# PSU_VCC3V3_Buck.net
KiCad netlist of a schematic drawn in Altium Designer
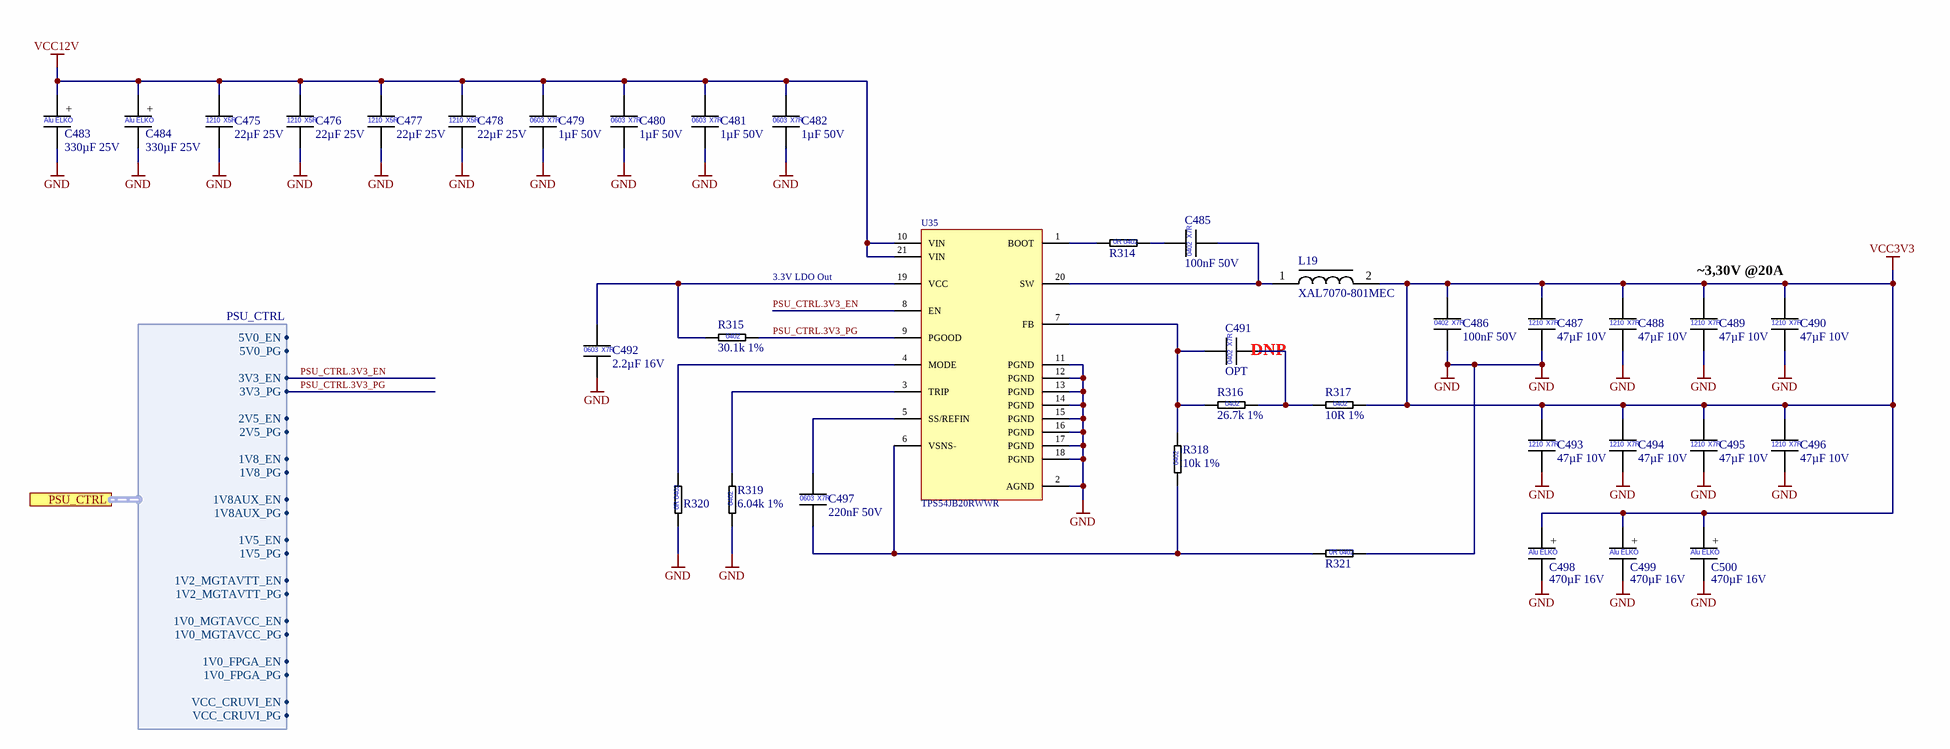
[diagram p0: PSU_VCC3V3_Buck.SchDoc]

(export (version "E")
  (design (tool "Eeschema 10.0.6"))
  (components
    (comp (ref "C475")
      (value "22µF 25V")
      (footprint "Cap:CAP_1210")
      (description "Multilayer Ceramic Capacitors MLCC - SMD/SMT 1210 25VDC")
      (libsource (lib "Cap") (part "CAP_1210_22µF_25V"))
    )
    (comp (ref "C476")
      (value "22µF 25V")
      (footprint "Cap:CAP_1210")
      (description "Multilayer Ceramic Capacitors MLCC - SMD/SMT 1210 25VDC")
      (libsource (lib "Cap") (part "CAP_1210_22µF_25V"))
    )
    (comp (ref "C477")
      (value "22µF 25V")
      (footprint "Cap:CAP_1210")
      (description "Multilayer Ceramic Capacitors MLCC - SMD/SMT 1210 25VDC")
      (libsource (lib "Cap") (part "CAP_1210_22µF_25V"))
    )
    (comp (ref "C478")
      (value "22µF 25V")
      (footprint "Cap:CAP_1210")
      (description "Multilayer Ceramic Capacitors MLCC - SMD/SMT 1210 25VDC")
      (libsource (lib "Cap") (part "CAP_1210_22µF_25V"))
    )
    (comp (ref "C479")
      (value "1µF 50V")
      (footprint "CAP_0603")
      (description "Multilayer Ceramic Capacitors MLCC - SMD/SMT 50V 1uF X7R 0603 10%")
      (libsource (lib "Cap") (part "CAP_0603_1µF_50V_X7R_10%"))
    )
    (comp (ref "C480")
      (value "1µF 50V")
      (footprint "CAP_0603")
      (description "Multilayer Ceramic Capacitors MLCC - SMD/SMT 50V 1uF X7R 0603 10%")
      (libsource (lib "Cap") (part "CAP_0603_1µF_50V_X7R_10%"))
    )
    (comp (ref "C481")
      (value "1µF 50V")
      (footprint "CAP_0603")
      (description "Multilayer Ceramic Capacitors MLCC - SMD/SMT 50V 1uF X7R 0603 10%")
      (libsource (lib "Cap") (part "CAP_0603_1µF_50V_X7R_10%"))
    )
    (comp (ref "C482")
      (value "1µF 50V")
      (footprint "CAP_0603")
      (description "Multilayer Ceramic Capacitors MLCC - SMD/SMT 50V 1uF X7R 0603 10%")
      (libsource (lib "Cap") (part "CAP_0603_1µF_50V_X7R_10%"))
    )
    (comp (ref "C483")
      (value "330µF 25V")
      (footprint "Cap:WCAP-PTG5_D10H12.5")
      (description "Organische Polymer-Aluminiumkondensatoren 330uF 25 Volts 20% AEC-Q200")
      (libsource (lib "Cap") (part "CAP_D10L12.5_330µF_25V"))
    )
    (comp (ref "C484")
      (value "330µF 25V")
      (footprint "Cap:WCAP-PTG5_D10H12.5")
      (description "Organische Polymer-Aluminiumkondensatoren 330uF 25 Volts 20% AEC-Q200")
      (libsource (lib "Cap") (part "CAP_D10L12.5_330µF_25V"))
    )
    (comp (ref "C485")
      (value "100nF 50V")
      (footprint "Cap:CAP_0402")
      (description "Multilayer Ceramic Capacitors MLCC - SMD/SMT 0402 50VDC")
      (libsource (lib "") (part "CAP_0402_100nF_50V_1"))
    )
    (comp (ref "C486")
      (value "100nF 50V")
      (footprint "Cap:CAP_0402")
      (description "Multilayer Ceramic Capacitors MLCC - SMD/SMT 0402 50VDC")
      (libsource (lib "Cap") (part "CAP_0402_100nF_50V"))
    )
    (comp (ref "C487")
      (value "47µF 10V")
      (footprint "Cap:CAP_1210")
      (description "Multilayer Ceramic Capacitors MLCC - SMD/SMT 47 uF 10 VDC 10% 1210 X7R")
      (libsource (lib "Cap") (part "CAP_1210_47µF_10V_X7R_10%"))
    )
    (comp (ref "C488")
      (value "47µF 10V")
      (footprint "Cap:CAP_1210")
      (description "Multilayer Ceramic Capacitors MLCC - SMD/SMT 47 uF 10 VDC 10% 1210 X7R")
      (libsource (lib "Cap") (part "CAP_1210_47µF_10V_X7R_10%"))
    )
    (comp (ref "C489")
      (value "47µF 10V")
      (footprint "Cap:CAP_1210")
      (description "Multilayer Ceramic Capacitors MLCC - SMD/SMT 47 uF 10 VDC 10% 1210 X7R")
      (libsource (lib "Cap") (part "CAP_1210_47µF_10V_X7R_10%"))
    )
    (comp (ref "C490")
      (value "47µF 10V")
      (footprint "Cap:CAP_1210")
      (description "Multilayer Ceramic Capacitors MLCC - SMD/SMT 47 uF 10 VDC 10% 1210 X7R")
      (libsource (lib "Cap") (part "CAP_1210_47µF_10V_X7R_10%"))
    )
    (comp (ref "C491")
      (value "OPT")
      (footprint "Cap:CAP_0402")
      (description "Multilayer Ceramic Capacitors MLCC - SMD/SMT 0402 Optional Placeholder")
      (libsource (lib "Cap") (part "CAP_0402_OPT"))
    )
    (comp (ref "C492")
      (value "2.2µF 16V")
      (footprint "Cap:CAP_0603")
      (description "Multilayer Ceramic Capacitors MLCC - SMD/SMT 2.2 uF 16 VDC 10% 0603 X7R")
      (libsource (lib "Cap") (part "CAP_0603_2.2µF_16V_X7R_10%"))
    )
    (comp (ref "C493")
      (value "47µF 10V")
      (footprint "Cap:CAP_1210")
      (description "Multilayer Ceramic Capacitors MLCC - SMD/SMT 47 uF 10 VDC 10% 1210 X7R")
      (libsource (lib "Cap") (part "CAP_1210_47µF_10V_X7R_10%"))
    )
    (comp (ref "C494")
      (value "47µF 10V")
      (footprint "Cap:CAP_1210")
      (description "Multilayer Ceramic Capacitors MLCC - SMD/SMT 47 uF 10 VDC 10% 1210 X7R")
      (libsource (lib "Cap") (part "CAP_1210_47µF_10V_X7R_10%"))
    )
    (comp (ref "C495")
      (value "47µF 10V")
      (footprint "Cap:CAP_1210")
      (description "Multilayer Ceramic Capacitors MLCC - SMD/SMT 47 uF 10 VDC 10% 1210 X7R")
      (libsource (lib "Cap") (part "CAP_1210_47µF_10V_X7R_10%"))
    )
    (comp (ref "C496")
      (value "47µF 10V")
      (footprint "Cap:CAP_1210")
      (description "Multilayer Ceramic Capacitors MLCC - SMD/SMT 47 uF 10 VDC 10% 1210 X7R")
      (libsource (lib "Cap") (part "CAP_1210_47µF_10V_X7R_10%"))
    )
    (comp (ref "C497")
      (value "220nF 50V")
      (footprint "CAP_0603")
      (description "Multilayer Ceramic Capacitors MLCC - SMD/SMT 0.22 uF 50 VDC 10% 0603 X7R")
      (libsource (lib "Cap") (part "CAP_0603_220nF_50V_X7R_10%"))
    )
    (comp (ref "C498")
      (value "470µF 16V")
      (footprint "Cap:WCAP-PTG5_D8H13")
      (description "Organische Polymer-Aluminiumkondensatoren 470uF 16 Volts 20%")
      (libsource (lib "Cap") (part "CAP_D8L9_470µF_16V"))
    )
    (comp (ref "C499")
      (value "470µF 16V")
      (footprint "Cap:WCAP-PTG5_D8H13")
      (description "Organische Polymer-Aluminiumkondensatoren 470uF 16 Volts 20%")
      (libsource (lib "Cap") (part "CAP_D8L9_470µF_16V"))
    )
    (comp (ref "C500")
      (value "470µF 16V")
      (footprint "Cap:WCAP-PTG5_D8H13")
      (description "Organische Polymer-Aluminiumkondensatoren 470uF 16 Volts 20%")
      (libsource (lib "Cap") (part "CAP_D8L9_470µF_16V"))
    )
    (comp (ref "L19")
      (value "XAL7070-801MEC")
      (footprint "indc:COILCRAFT_XAL7070")
      (description "Power Inductors - SMD 800nH Shld 20% 25.8A 2.29mOhms AECQ200")
      (libsource (lib "Indc") (part "XAL7070-801MEC_Power Inductors SMD 800nH Shld 20% 25.8A 2.29mOhms AECQ200"))
    )
    (comp (ref "R314")
      (value "0R Jumper")
      (footprint "res:RES_0402")
      (description "Thick Film Resistors - SMD 0Ohm")
      (libsource (lib "Res") (part "RES_0402_0R Jumper"))
    )
    (comp (ref "R315")
      (value "30.1k 1%")
      (footprint "res:RES_0402")
      (description "Thick Film Resistors - SMD 30.1kOhm 1%")
      (libsource (lib "Res") (part "RES_0402_30.1k_1%"))
    )
    (comp (ref "R316")
      (value "26.7k 1%")
      (footprint "res:RES_0402")
      (description "Thick Film Resistors - SMD 26.7kOhm 1%")
      (libsource (lib "Res") (part "RES_0402_26.7k_1%"))
    )
    (comp (ref "R317")
      (value "10R 1%")
      (footprint "res:RES_0402")
      (description "Thick Film Resistors - SMD 10Ohm 1%")
      (libsource (lib "Res") (part "RES_0402_10R_1%"))
    )
    (comp (ref "R318")
      (value "10k 1%")
      (footprint "Res:RES_0402")
      (description "Thick Film Resistors - SMD 10kOhm 1%")
      (libsource (lib "Res") (part "RES_0402_10k_1%"))
    )
    (comp (ref "R319")
      (value "6.04k 1%")
      (footprint "Res:RES_0402")
      (description "Thick Film Resistors - SMD 6.04kOhm 1%")
      (libsource (lib "Res") (part "RES_0402_6.04k_1%"))
    )
    (comp (ref "R320")
      (value "0R Jumper")
      (footprint "res:RES_0402")
      (description "Thick Film Resistors - SMD 0Ohm")
      (libsource (lib "Res") (part "RES_0402_0R Jumper"))
    )
    (comp (ref "R321")
      (value "0R Jumper")
      (footprint "res:RES_0402")
      (description "Thick Film Resistors - SMD 0Ohm")
      (libsource (lib "Res") (part "RES_0402_0R Jumper"))
    )
    (comp (ref "U35")
      (value "TPS54JB20RWWR")
      (footprint "power:VQFN-HR21_RWW0021A")
      (description "Switching Voltage Regulators 2.7-V to 16-V input 20-A synchronous Buck")
      (libsource (lib "Power") (part "TPS54JB20RWWR_Switching Voltage Regulators 2.7-V to 16-V input 20-A synchronous Buck"))
    )
  )
  (nets
    (net (code "2") (name "/PSU_CTRL.3V3_EN") (class "Default")
      (node (ref "U35") (pin "8") (pinfunction "EN_8") (pintype "passive"))
    )
    (net (code "3") (name "/PSU_CTRL.3V3_PG") (class "Default")
      (node (ref "R315") (pin "2") (pinfunction "2_2") (pintype "passive"))
      (node (ref "U35") (pin "9") (pinfunction "PGOOD_9") (pintype "passive"))
    )
    (net (code "5") (name "GND") (class "Default")
      (node (ref "C475") (pin "2") (pinfunction "2_2") (pintype "passive"))
      (node (ref "C476") (pin "2") (pinfunction "2_2") (pintype "passive"))
      (node (ref "C477") (pin "2") (pinfunction "2_2") (pintype "passive"))
      (node (ref "C478") (pin "2") (pinfunction "2_2") (pintype "passive"))
      (node (ref "C479") (pin "2") (pinfunction "2_2") (pintype "passive"))
      (node (ref "C480") (pin "2") (pinfunction "2_2") (pintype "passive"))
      (node (ref "C481") (pin "2") (pinfunction "2_2") (pintype "passive"))
      (node (ref "C482") (pin "2") (pinfunction "2_2") (pintype "passive"))
      (node (ref "C483") (pin "2") (pinfunction "2_2") (pintype "passive"))
      (node (ref "C484") (pin "2") (pinfunction "2_2") (pintype "passive"))
      (node (ref "C486") (pin "2") (pinfunction "2_2") (pintype "passive"))
      (node (ref "C487") (pin "2") (pinfunction "2_2") (pintype "passive"))
      (node (ref "C488") (pin "2") (pinfunction "2_2") (pintype "passive"))
      (node (ref "C489") (pin "2") (pinfunction "2_2") (pintype "passive"))
      (node (ref "C490") (pin "2") (pinfunction "2_2") (pintype "passive"))
      (node (ref "C492") (pin "2") (pinfunction "2_2") (pintype "passive"))
      (node (ref "C493") (pin "2") (pinfunction "2_2") (pintype "passive"))
      (node (ref "C494") (pin "2") (pinfunction "2_2") (pintype "passive"))
      (node (ref "C495") (pin "2") (pinfunction "2_2") (pintype "passive"))
      (node (ref "C496") (pin "2") (pinfunction "2_2") (pintype "passive"))
      (node (ref "C498") (pin "2") (pinfunction "2_2") (pintype "passive"))
      (node (ref "C499") (pin "2") (pinfunction "2_2") (pintype "passive"))
      (node (ref "C500") (pin "2") (pinfunction "2_2") (pintype "passive"))
      (node (ref "R319") (pin "1") (pinfunction "1_1") (pintype "passive"))
      (node (ref "R320") (pin "1") (pinfunction "1_1") (pintype "passive"))
      (node (ref "R321") (pin "2") (pinfunction "2_2") (pintype "passive"))
      (node (ref "U35") (pin "11") (pinfunction "PGND_11") (pintype "passive"))
      (node (ref "U35") (pin "12") (pinfunction "PGND_12") (pintype "passive"))
      (node (ref "U35") (pin "13") (pinfunction "PGND_13") (pintype "passive"))
      (node (ref "U35") (pin "14") (pinfunction "PGND_14") (pintype "passive"))
      (node (ref "U35") (pin "15") (pinfunction "PGND_15") (pintype "passive"))
      (node (ref "U35") (pin "16") (pinfunction "PGND_16") (pintype "passive"))
      (node (ref "U35") (pin "17") (pinfunction "PGND_17") (pintype "passive"))
      (node (ref "U35") (pin "18") (pinfunction "PGND_18") (pintype "passive"))
      (node (ref "U35") (pin "2") (pinfunction "AGND_2") (pintype "passive"))
    )
    (net (code "6") (name "Net-(C485-Pad1)") (class "Default")
      (node (ref "C485") (pin "1") (pinfunction "1_1") (pintype "passive"))
      (node (ref "R314") (pin "2") (pinfunction "2_2") (pintype "passive"))
    )
    (net (code "7") (name "Net-(C491-Pad2)") (class "Default")
      (node (ref "C491") (pin "2") (pinfunction "2_2") (pintype "passive"))
      (node (ref "R316") (pin "2") (pinfunction "2_2") (pintype "passive"))
      (node (ref "R317") (pin "1") (pinfunction "1_1") (pintype "passive"))
    )
    (net (code "8") (name "Net-(U35-BOOT)") (class "Default")
      (node (ref "R314") (pin "1") (pinfunction "1_1") (pintype "passive"))
      (node (ref "U35") (pin "1") (pinfunction "BOOT_1") (pintype "passive"))
    )
    (net (code "9") (name "Net-(U35-FB)") (class "Default")
      (node (ref "C491") (pin "1") (pinfunction "1_1") (pintype "passive"))
      (node (ref "R316") (pin "1") (pinfunction "1_1") (pintype "passive"))
      (node (ref "R318") (pin "2") (pinfunction "2_2") (pintype "passive"))
      (node (ref "U35") (pin "7") (pinfunction "FB_7") (pintype "passive"))
    )
    (net (code "10") (name "Net-(U35-MODE)") (class "Default")
      (node (ref "R320") (pin "2") (pinfunction "2_2") (pintype "passive"))
      (node (ref "U35") (pin "4") (pinfunction "MODE_4") (pintype "passive"))
    )
    (net (code "11") (name "Net-(U35-SS{slash}REFIN)") (class "Default")
      (node (ref "C497") (pin "1") (pinfunction "1_1") (pintype "passive"))
      (node (ref "U35") (pin "5") (pinfunction "SS/REFIN_5") (pintype "passive"))
    )
    (net (code "12") (name "Net-(U35-SW)") (class "Default")
      (node (ref "C485") (pin "2") (pinfunction "2_2") (pintype "passive"))
      (node (ref "L19") (pin "1") (pinfunction "1_1") (pintype "passive"))
      (node (ref "U35") (pin "20") (pinfunction "SW_20") (pintype "passive"))
    )
    (net (code "13") (name "Net-(U35-TRIP)") (class "Default")
      (node (ref "R319") (pin "2") (pinfunction "2_2") (pintype "passive"))
      (node (ref "U35") (pin "3") (pinfunction "TRIP_3") (pintype "passive"))
    )
    (net (code "14") (name "Net-(U35-VCC)") (class "Default")
      (node (ref "C492") (pin "1") (pinfunction "1_1") (pintype "passive"))
      (node (ref "R315") (pin "1") (pinfunction "1_1") (pintype "passive"))
      (node (ref "U35") (pin "19") (pinfunction "VCC_19") (pintype "passive"))
    )
    (net (code "15") (name "Net-(U35-VSNS-)") (class "Default")
      (node (ref "C497") (pin "2") (pinfunction "2_2") (pintype "passive"))
      (node (ref "R318") (pin "1") (pinfunction "1_1") (pintype "passive"))
      (node (ref "R321") (pin "1") (pinfunction "1_1") (pintype "passive"))
      (node (ref "U35") (pin "6") (pinfunction "VSNS-_6") (pintype "passive"))
    )
    (net (code "16") (name "VCC3V3") (class "Default")
      (node (ref "C486") (pin "1") (pinfunction "1_1") (pintype "passive"))
      (node (ref "C487") (pin "1") (pinfunction "1_1") (pintype "passive"))
      (node (ref "C488") (pin "1") (pinfunction "1_1") (pintype "passive"))
      (node (ref "C489") (pin "1") (pinfunction "1_1") (pintype "passive"))
      (node (ref "C490") (pin "1") (pinfunction "1_1") (pintype "passive"))
      (node (ref "C493") (pin "1") (pinfunction "1_1") (pintype "passive"))
      (node (ref "C494") (pin "1") (pinfunction "1_1") (pintype "passive"))
      (node (ref "C495") (pin "1") (pinfunction "1_1") (pintype "passive"))
      (node (ref "C496") (pin "1") (pinfunction "1_1") (pintype "passive"))
      (node (ref "C498") (pin "1") (pinfunction "1_1") (pintype "passive"))
      (node (ref "C499") (pin "1") (pinfunction "1_1") (pintype "passive"))
      (node (ref "C500") (pin "1") (pinfunction "1_1") (pintype "passive"))
      (node (ref "L19") (pin "2") (pinfunction "2_2") (pintype "passive"))
      (node (ref "R317") (pin "2") (pinfunction "2_2") (pintype "passive"))
    )
    (net (code "17") (name "VCC12V") (class "Default")
      (node (ref "C475") (pin "1") (pinfunction "1_1") (pintype "passive"))
      (node (ref "C476") (pin "1") (pinfunction "1_1") (pintype "passive"))
      (node (ref "C477") (pin "1") (pinfunction "1_1") (pintype "passive"))
      (node (ref "C478") (pin "1") (pinfunction "1_1") (pintype "passive"))
      (node (ref "C479") (pin "1") (pinfunction "1_1") (pintype "passive"))
      (node (ref "C480") (pin "1") (pinfunction "1_1") (pintype "passive"))
      (node (ref "C481") (pin "1") (pinfunction "1_1") (pintype "passive"))
      (node (ref "C482") (pin "1") (pinfunction "1_1") (pintype "passive"))
      (node (ref "C483") (pin "1") (pinfunction "1_1") (pintype "passive"))
      (node (ref "C484") (pin "1") (pinfunction "1_1") (pintype "passive"))
      (node (ref "U35") (pin "10") (pinfunction "VIN_10") (pintype "passive"))
      (node (ref "U35") (pin "21") (pinfunction "VIN_21") (pintype "passive"))
    )
  )
)
